# TimerSchematicV1.net
KiCad netlist of a schematic drawn in EAGLE
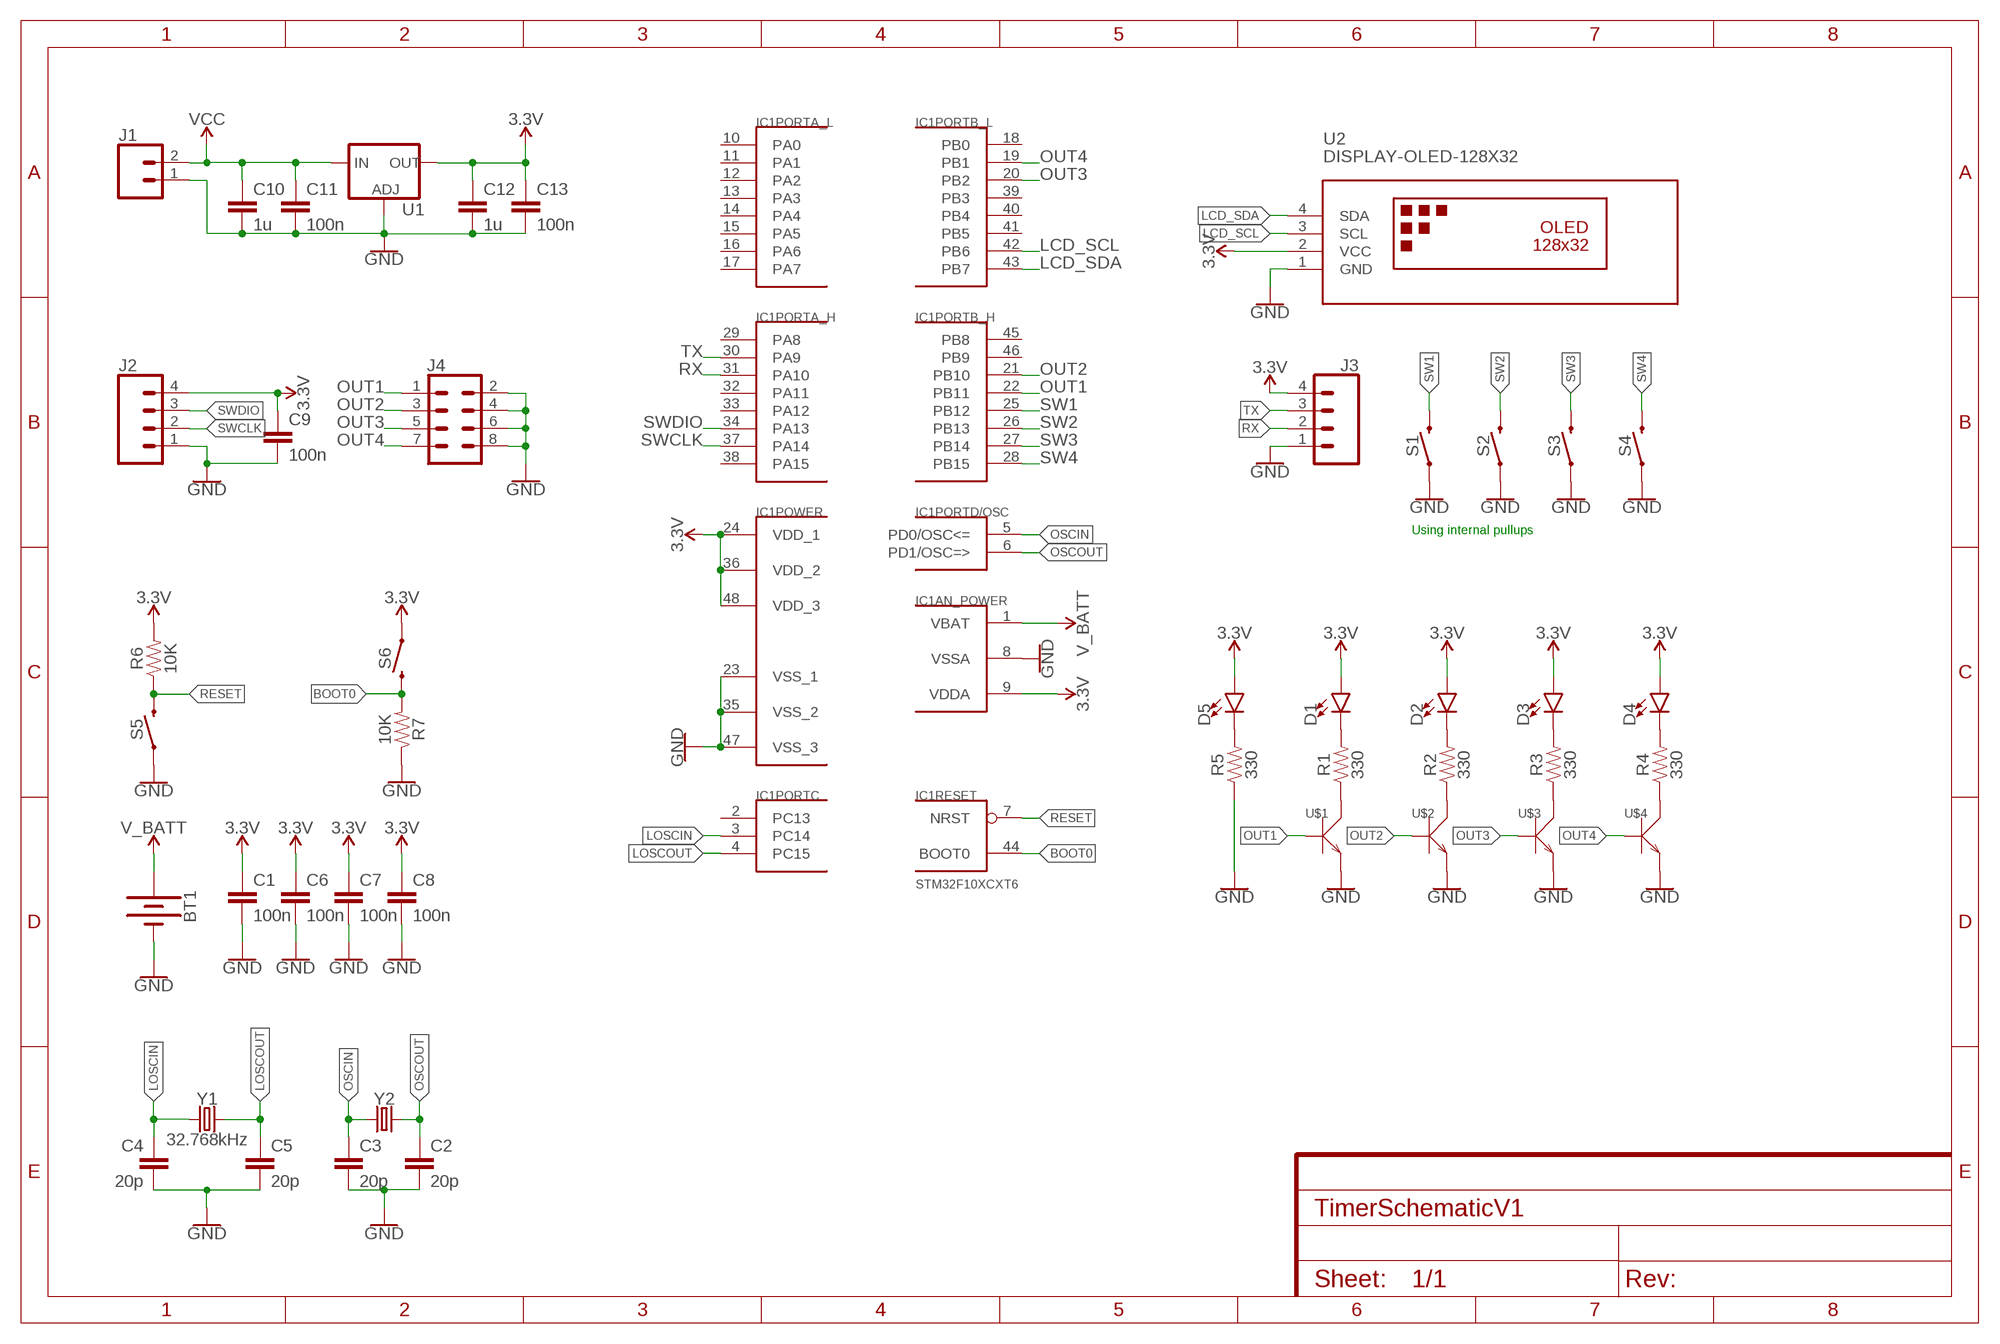
[diagram p0: schematic, sheet 1]

(export (version "E")
  (design (tool "Eeschema 10.0.6"))
  (components
    (comp (ref "BT1")
      (value "BATTERY-20MM_PTH")
      (footprint "eagle-import:BATTCOM_20MM_PTH")
      (libsource (lib "eagle-import") (part "BATTERY-20MM_PTH"))
    )
    (comp (ref "C1")
      (value "100n")
      (footprint "eagle-import:1206")
      (libsource (lib "eagle-import") (part "CAP-1206"))
    )
    (comp (ref "C2")
      (value "20p")
      (footprint "eagle-import:1206")
      (libsource (lib "eagle-import") (part "CAP-1206"))
    )
    (comp (ref "C3")
      (value "20p")
      (footprint "eagle-import:1206")
      (libsource (lib "eagle-import") (part "CAP-1206"))
    )
    (comp (ref "C4")
      (value "20p")
      (footprint "eagle-import:1206")
      (libsource (lib "eagle-import") (part "CAP-1206"))
    )
    (comp (ref "C5")
      (value "20p")
      (footprint "eagle-import:1206")
      (libsource (lib "eagle-import") (part "CAP-1206"))
    )
    (comp (ref "C6")
      (value "100n")
      (footprint "eagle-import:1206")
      (libsource (lib "eagle-import") (part "CAP-1206"))
    )
    (comp (ref "C7")
      (value "100n")
      (footprint "eagle-import:1206")
      (libsource (lib "eagle-import") (part "CAP-1206"))
    )
    (comp (ref "C8")
      (value "100n")
      (footprint "eagle-import:1206")
      (libsource (lib "eagle-import") (part "CAP-1206"))
    )
    (comp (ref "C9")
      (value "100n")
      (footprint "eagle-import:1206")
      (libsource (lib "eagle-import") (part "CAP-1206"))
    )
    (comp (ref "C10")
      (value "1u")
      (footprint "eagle-import:1206")
      (libsource (lib "eagle-import") (part "CAP-1206"))
    )
    (comp (ref "C11")
      (value "100n")
      (footprint "eagle-import:1206")
      (libsource (lib "eagle-import") (part "CAP-1206"))
    )
    (comp (ref "C12")
      (value "1u")
      (footprint "eagle-import:1206")
      (libsource (lib "eagle-import") (part "CAP-1206"))
    )
    (comp (ref "C13")
      (value "100n")
      (footprint "eagle-import:1206")
      (libsource (lib "eagle-import") (part "CAP-1206"))
    )
    (comp (ref "D1")
      (value "LED1206")
      (footprint "eagle-import:LED-1206")
      (libsource (lib "eagle-import") (part "LED1206"))
    )
    (comp (ref "D2")
      (value "LED1206")
      (footprint "eagle-import:LED-1206")
      (libsource (lib "eagle-import") (part "LED1206"))
    )
    (comp (ref "D3")
      (value "LED1206")
      (footprint "eagle-import:LED-1206")
      (libsource (lib "eagle-import") (part "LED1206"))
    )
    (comp (ref "D4")
      (value "LED1206")
      (footprint "eagle-import:LED-1206")
      (libsource (lib "eagle-import") (part "LED1206"))
    )
    (comp (ref "D5")
      (value "LED1206")
      (footprint "eagle-import:LED-1206")
      (libsource (lib "eagle-import") (part "LED1206"))
    )
    (comp (ref "IC1")
      (value "STM32F10XCXT6")
      (footprint "eagle-import:TQFP48")
      (libsource (lib "eagle-import") (part "STM32F10XCXT6"))
    )
    (comp (ref "J1")
      (value "CONN_02")
      (footprint "eagle-import:1X02")
      (libsource (lib "eagle-import") (part "CONN_02"))
    )
    (comp (ref "J2")
      (value "CONN_04PTH")
      (footprint "eagle-import:1X04")
      (libsource (lib "eagle-import") (part "CONN_04PTH"))
    )
    (comp (ref "J3")
      (value "CONN_04PTH")
      (footprint "eagle-import:1X04")
      (libsource (lib "eagle-import") (part "CONN_04PTH"))
    )
    (comp (ref "J4")
      (value "CONN_04X2")
      (footprint "eagle-import:2X4")
      (libsource (lib "eagle-import") (part "CONN_04X2"))
    )
    (comp (ref "R1")
      (value "330")
      (footprint "eagle-import:1206")
      (libsource (lib "eagle-import") (part "RESISTOR1206"))
    )
    (comp (ref "R2")
      (value "330")
      (footprint "eagle-import:1206")
      (libsource (lib "eagle-import") (part "RESISTOR1206"))
    )
    (comp (ref "R3")
      (value "330")
      (footprint "eagle-import:1206")
      (libsource (lib "eagle-import") (part "RESISTOR1206"))
    )
    (comp (ref "R4")
      (value "330")
      (footprint "eagle-import:1206")
      (libsource (lib "eagle-import") (part "RESISTOR1206"))
    )
    (comp (ref "R5")
      (value "330")
      (footprint "eagle-import:1206")
      (libsource (lib "eagle-import") (part "RESISTOR1206"))
    )
    (comp (ref "R6")
      (value "10K")
      (footprint "eagle-import:1206")
      (libsource (lib "eagle-import") (part "RESISTOR1206"))
    )
    (comp (ref "R7")
      (value "10K")
      (footprint "eagle-import:1206")
      (libsource (lib "eagle-import") (part "RESISTOR1206"))
    )
    (comp (ref "S1")
      (value "MOMENTARY-SWITCH-SPST-PTH-6.0MM-KIT")
      (footprint "eagle-import:TACTILE_SWITCH_PTH_6.0MM_KIT")
      (libsource (lib "eagle-import") (part "MOMENTARY-SWITCH-SPST-PTH-6.0MM-KIT"))
    )
    (comp (ref "S2")
      (value "MOMENTARY-SWITCH-SPST-PTH-6.0MM-KIT")
      (footprint "eagle-import:TACTILE_SWITCH_PTH_6.0MM_KIT")
      (libsource (lib "eagle-import") (part "MOMENTARY-SWITCH-SPST-PTH-6.0MM-KIT"))
    )
    (comp (ref "S3")
      (value "MOMENTARY-SWITCH-SPST-PTH-6.0MM-KIT")
      (footprint "eagle-import:TACTILE_SWITCH_PTH_6.0MM_KIT")
      (libsource (lib "eagle-import") (part "MOMENTARY-SWITCH-SPST-PTH-6.0MM-KIT"))
    )
    (comp (ref "S4")
      (value "MOMENTARY-SWITCH-SPST-PTH-6.0MM-KIT")
      (footprint "eagle-import:TACTILE_SWITCH_PTH_6.0MM_KIT")
      (libsource (lib "eagle-import") (part "MOMENTARY-SWITCH-SPST-PTH-6.0MM-KIT"))
    )
    (comp (ref "S5")
      (value "MOMENTARY-SWITCH-SPST-SMD-6.0X3.5MM")
      (footprint "eagle-import:TACTILE_SWITCH_SMD_6.0X3.5MM")
      (libsource (lib "eagle-import") (part "MOMENTARY-SWITCH-SPST-SMD-6.0X3.5MM"))
    )
    (comp (ref "S6")
      (value "MOMENTARY-SWITCH-SPST-SMD-6.0X3.5MM")
      (footprint "eagle-import:TACTILE_SWITCH_SMD_6.0X3.5MM")
      (libsource (lib "eagle-import") (part "MOMENTARY-SWITCH-SPST-SMD-6.0X3.5MM"))
    )
    (comp (ref "U$1")
      (value "MMBT3904LT1G")
      (footprint "eagle-import:SOT-23")
      (libsource (lib "eagle-import") (part "SMD-TRANSISTORS-NPN-40V-200MA-MMBT3904LT1G(SOT-23)"))
    )
    (comp (ref "U$2")
      (value "MMBT3904LT1G")
      (footprint "eagle-import:SOT-23")
      (libsource (lib "eagle-import") (part "SMD-TRANSISTORS-NPN-40V-200MA-MMBT3904LT1G(SOT-23)"))
    )
    (comp (ref "U$3")
      (value "MMBT3904LT1G")
      (footprint "eagle-import:SOT-23")
      (libsource (lib "eagle-import") (part "SMD-TRANSISTORS-NPN-40V-200MA-MMBT3904LT1G(SOT-23)"))
    )
    (comp (ref "U$4")
      (value "MMBT3904LT1G")
      (footprint "eagle-import:SOT-23")
      (libsource (lib "eagle-import") (part "SMD-TRANSISTORS-NPN-40V-200MA-MMBT3904LT1G(SOT-23)"))
    )
    (comp (ref "U1")
      (value "V_REG_LM1117SOT223")
      (footprint "eagle-import:SOT223")
      (libsource (lib "eagle-import") (part "V_REG_LM1117SOT223"))
    )
    (comp (ref "U2")
      (value "DISPLAY-OLED-128X32")
      (footprint "eagle-import:DISPLAY-OLED-128X32")
      (libsource (lib "eagle-import") (part "DISPLAY-OLED-128X32"))
    )
    (comp (ref "Y1")
      (value "32.768kHz")
      (footprint "eagle-import:CRYSTAL-PTH-2X6-CYL-KIT")
      (libsource (lib "eagle-import") (part "CRYSTAL-32.768KHZPTH-2X6-KIT"))
    )
    (comp (ref "Y2")
      (value "CRYSTALSMD-HC49UP")
      (footprint "eagle-import:HC49UP")
      (libsource (lib "eagle-import") (part "CRYSTALSMD-HC49UP"))
    )
  )
  (nets
    (net (code "1") (name "3.3V") (class "Default")
      (node (ref "C1") (pin "1") (pinfunction "1_1") (pintype "passive"))
      (node (ref "C12") (pin "1") (pinfunction "1_1") (pintype "passive"))
      (node (ref "C13") (pin "1") (pinfunction "1_1") (pintype "passive"))
      (node (ref "C6") (pin "1") (pinfunction "1_1") (pintype "passive"))
      (node (ref "C7") (pin "1") (pinfunction "1_1") (pintype "passive"))
      (node (ref "C8") (pin "1") (pinfunction "1_1") (pintype "passive"))
      (node (ref "C9") (pin "1") (pinfunction "1_1") (pintype "passive"))
      (node (ref "D1") (pin "A") (pinfunction "A_A") (pintype "passive"))
      (node (ref "D2") (pin "A") (pinfunction "A_A") (pintype "passive"))
      (node (ref "D3") (pin "A") (pinfunction "A_A") (pintype "passive"))
      (node (ref "D4") (pin "A") (pinfunction "A_A") (pintype "passive"))
      (node (ref "D5") (pin "A") (pinfunction "A_A") (pintype "passive"))
      (node (ref "IC1") (pin "24") (pinfunction "VDD_1_24") (pintype "power_in"))
      (node (ref "IC1") (pin "36") (pinfunction "VDD_2_36") (pintype "power_in"))
      (node (ref "IC1") (pin "48") (pinfunction "VDD_3_48") (pintype "power_in"))
      (node (ref "IC1") (pin "9") (pinfunction "VDDA_9") (pintype "power_in"))
      (node (ref "J2") (pin "4") (pinfunction "4_4") (pintype "passive"))
      (node (ref "J3") (pin "4") (pinfunction "4_4") (pintype "passive"))
      (node (ref "R6") (pin "2") (pinfunction "2_2") (pintype "passive"))
      (node (ref "S6") (pin "1") (pinfunction "1_1") (pintype "passive"))
      (node (ref "U1") (pin "2") (pinfunction "OUT_2") (pintype "output"))
      (node (ref "U1") (pin "4") (pinfunction "OUT_4") (pintype "output"))
      (node (ref "U2") (pin "2") (pinfunction "VCC_2") (pintype "power_in"))
    )
    (net (code "2") (name "BOOT0") (class "Default")
      (node (ref "IC1") (pin "44") (pinfunction "BOOT0_44") (pintype "input"))
      (node (ref "R7") (pin "2") (pinfunction "2_2") (pintype "passive"))
      (node (ref "S6") (pin "2") (pinfunction "2_2") (pintype "passive"))
    )
    (net (code "3") (name "GND") (class "Default")
      (node (ref "BT1") (pin "2") (pinfunction "-_2") (pintype "power_in"))
      (node (ref "C1") (pin "2") (pinfunction "2_2") (pintype "passive"))
      (node (ref "C10") (pin "2") (pinfunction "2_2") (pintype "passive"))
      (node (ref "C11") (pin "2") (pinfunction "2_2") (pintype "passive"))
      (node (ref "C12") (pin "2") (pinfunction "2_2") (pintype "passive"))
      (node (ref "C13") (pin "2") (pinfunction "2_2") (pintype "passive"))
      (node (ref "C2") (pin "2") (pinfunction "2_2") (pintype "passive"))
      (node (ref "C3") (pin "2") (pinfunction "2_2") (pintype "passive"))
      (node (ref "C4") (pin "2") (pinfunction "2_2") (pintype "passive"))
      (node (ref "C5") (pin "2") (pinfunction "2_2") (pintype "passive"))
      (node (ref "C6") (pin "2") (pinfunction "2_2") (pintype "passive"))
      (node (ref "C7") (pin "2") (pinfunction "2_2") (pintype "passive"))
      (node (ref "C8") (pin "2") (pinfunction "2_2") (pintype "passive"))
      (node (ref "C9") (pin "2") (pinfunction "2_2") (pintype "passive"))
      (node (ref "IC1") (pin "23") (pinfunction "VSS_1_23") (pintype "power_in"))
      (node (ref "IC1") (pin "35") (pinfunction "VSS_2_35") (pintype "power_in"))
      (node (ref "IC1") (pin "47") (pinfunction "VSS_3_47") (pintype "power_in"))
      (node (ref "IC1") (pin "8") (pinfunction "VSSA_8") (pintype "power_in"))
      (node (ref "J1") (pin "1") (pinfunction "1_1") (pintype "passive"))
      (node (ref "J2") (pin "1") (pinfunction "1_1") (pintype "passive"))
      (node (ref "J3") (pin "1") (pinfunction "1_1") (pintype "passive"))
      (node (ref "J4") (pin "2") (pinfunction "2_2") (pintype "passive"))
      (node (ref "J4") (pin "4") (pinfunction "4_4") (pintype "passive"))
      (node (ref "J4") (pin "6") (pinfunction "6_6") (pintype "passive"))
      (node (ref "J4") (pin "8") (pinfunction "8_8") (pintype "passive"))
      (node (ref "R5") (pin "1") (pinfunction "1_1") (pintype "passive"))
      (node (ref "R7") (pin "1") (pinfunction "1_1") (pintype "passive"))
      (node (ref "S1") (pin "1") (pinfunction "1_1") (pintype "passive"))
      (node (ref "S2") (pin "1") (pinfunction "1_1") (pintype "passive"))
      (node (ref "S3") (pin "1") (pinfunction "1_1") (pintype "passive"))
      (node (ref "S4") (pin "1") (pinfunction "1_1") (pintype "passive"))
      (node (ref "S5") (pin "1") (pinfunction "1_1") (pintype "passive"))
      (node (ref "U$1") (pin "2") (pinfunction "E_2") (pintype "passive"))
      (node (ref "U$2") (pin "2") (pinfunction "E_2") (pintype "passive"))
      (node (ref "U$3") (pin "2") (pinfunction "E_2") (pintype "passive"))
      (node (ref "U$4") (pin "2") (pinfunction "E_2") (pintype "passive"))
      (node (ref "U1") (pin "1") (pinfunction "ADJ_1") (pintype "input"))
      (node (ref "U2") (pin "1") (pinfunction "GND_1") (pintype "power_in"))
    )
    (net (code "4") (name "LCD_SCL") (class "Default")
      (node (ref "IC1") (pin "42") (pinfunction "PB6_42") (pintype "bidirectional"))
      (node (ref "U2") (pin "3") (pinfunction "SCL_3") (pintype "bidirectional"))
    )
    (net (code "5") (name "LCD_SDA") (class "Default")
      (node (ref "IC1") (pin "43") (pinfunction "PB7_43") (pintype "bidirectional"))
      (node (ref "U2") (pin "4") (pinfunction "SDA_4") (pintype "bidirectional"))
    )
    (net (code "6") (name "LOSCIN") (class "Default")
      (node (ref "C4") (pin "1") (pinfunction "1_1") (pintype "passive"))
      (node (ref "IC1") (pin "3") (pinfunction "PC14_3") (pintype "bidirectional"))
      (node (ref "Y1") (pin "1") (pinfunction "1_1") (pintype "passive"))
    )
    (net (code "7") (name "LOSCOUT") (class "Default")
      (node (ref "C5") (pin "1") (pinfunction "1_1") (pintype "passive"))
      (node (ref "IC1") (pin "4") (pinfunction "PC15_4") (pintype "bidirectional"))
      (node (ref "Y1") (pin "2") (pinfunction "2_2") (pintype "passive"))
    )
    (net (code "8") (name "Net-(D1-PadC)") (class "Default")
      (node (ref "D1") (pin "C") (pinfunction "C_C") (pintype "passive"))
      (node (ref "R1") (pin "2") (pinfunction "2_2") (pintype "passive"))
    )
    (net (code "9") (name "Net-(D2-PadC)") (class "Default")
      (node (ref "D2") (pin "C") (pinfunction "C_C") (pintype "passive"))
      (node (ref "R2") (pin "2") (pinfunction "2_2") (pintype "passive"))
    )
    (net (code "10") (name "Net-(D3-PadC)") (class "Default")
      (node (ref "D3") (pin "C") (pinfunction "C_C") (pintype "passive"))
      (node (ref "R3") (pin "2") (pinfunction "2_2") (pintype "passive"))
    )
    (net (code "11") (name "Net-(D4-PadC)") (class "Default")
      (node (ref "D4") (pin "C") (pinfunction "C_C") (pintype "passive"))
      (node (ref "R4") (pin "2") (pinfunction "2_2") (pintype "passive"))
    )
    (net (code "12") (name "Net-(D5-PadC)") (class "Default")
      (node (ref "D5") (pin "C") (pinfunction "C_C") (pintype "passive"))
      (node (ref "R5") (pin "2") (pinfunction "2_2") (pintype "passive"))
    )
    (net (code "13") (name "Net-(U$1-C)") (class "Default")
      (node (ref "R1") (pin "1") (pinfunction "1_1") (pintype "passive"))
      (node (ref "U$1") (pin "3") (pinfunction "C_3") (pintype "passive"))
    )
    (net (code "14") (name "Net-(U$2-C)") (class "Default")
      (node (ref "R2") (pin "1") (pinfunction "1_1") (pintype "passive"))
      (node (ref "U$2") (pin "3") (pinfunction "C_3") (pintype "passive"))
    )
    (net (code "15") (name "Net-(U$3-C)") (class "Default")
      (node (ref "R3") (pin "1") (pinfunction "1_1") (pintype "passive"))
      (node (ref "U$3") (pin "3") (pinfunction "C_3") (pintype "passive"))
    )
    (net (code "16") (name "Net-(U$4-C)") (class "Default")
      (node (ref "R4") (pin "1") (pinfunction "1_1") (pintype "passive"))
      (node (ref "U$4") (pin "3") (pinfunction "C_3") (pintype "passive"))
    )
    (net (code "17") (name "OSCIN") (class "Default")
      (node (ref "C3") (pin "1") (pinfunction "1_1") (pintype "passive"))
      (node (ref "IC1") (pin "5") (pinfunction "PD0/OSC<=_5") (pintype "bidirectional"))
      (node (ref "Y2") (pin "1") (pinfunction "1_1") (pintype "passive"))
    )
    (net (code "18") (name "OSCOUT") (class "Default")
      (node (ref "C2") (pin "1") (pinfunction "1_1") (pintype "passive"))
      (node (ref "IC1") (pin "6") (pinfunction "PD1/OSC=>_6") (pintype "bidirectional"))
      (node (ref "Y2") (pin "2") (pinfunction "2_2") (pintype "passive"))
    )
    (net (code "19") (name "OUT1") (class "Default")
      (node (ref "IC1") (pin "22") (pinfunction "PB11_22") (pintype "bidirectional"))
      (node (ref "J4") (pin "1") (pinfunction "1_1") (pintype "passive"))
      (node (ref "U$1") (pin "1") (pinfunction "B_1") (pintype "passive"))
    )
    (net (code "20") (name "OUT2") (class "Default")
      (node (ref "IC1") (pin "21") (pinfunction "PB10_21") (pintype "bidirectional"))
      (node (ref "J4") (pin "3") (pinfunction "3_3") (pintype "passive"))
      (node (ref "U$2") (pin "1") (pinfunction "B_1") (pintype "passive"))
    )
    (net (code "21") (name "OUT3") (class "Default")
      (node (ref "IC1") (pin "20") (pinfunction "PB2_20") (pintype "bidirectional"))
      (node (ref "J4") (pin "5") (pinfunction "5_5") (pintype "passive"))
      (node (ref "U$3") (pin "1") (pinfunction "B_1") (pintype "passive"))
    )
    (net (code "22") (name "OUT4") (class "Default")
      (node (ref "IC1") (pin "19") (pinfunction "PB1_19") (pintype "bidirectional"))
      (node (ref "J4") (pin "7") (pinfunction "7_7") (pintype "passive"))
      (node (ref "U$4") (pin "1") (pinfunction "B_1") (pintype "passive"))
    )
    (net (code "23") (name "RESET") (class "Default")
      (node (ref "IC1") (pin "7") (pinfunction "NRST_7") (pintype "input"))
      (node (ref "R6") (pin "1") (pinfunction "1_1") (pintype "passive"))
      (node (ref "S5") (pin "2") (pinfunction "2_2") (pintype "passive"))
    )
    (net (code "24") (name "RX") (class "Default")
      (node (ref "IC1") (pin "31") (pinfunction "PA10_31") (pintype "bidirectional"))
      (node (ref "J3") (pin "2") (pinfunction "2_2") (pintype "passive"))
    )
    (net (code "25") (name "SW1") (class "Default")
      (node (ref "IC1") (pin "25") (pinfunction "PB12_25") (pintype "bidirectional"))
      (node (ref "S1") (pin "3") (pinfunction "2_3") (pintype "passive"))
    )
    (net (code "26") (name "SW2") (class "Default")
      (node (ref "IC1") (pin "26") (pinfunction "PB13_26") (pintype "bidirectional"))
      (node (ref "S2") (pin "3") (pinfunction "2_3") (pintype "passive"))
    )
    (net (code "27") (name "SW3") (class "Default")
      (node (ref "IC1") (pin "27") (pinfunction "PB14_27") (pintype "bidirectional"))
      (node (ref "S3") (pin "3") (pinfunction "2_3") (pintype "passive"))
    )
    (net (code "28") (name "SW4") (class "Default")
      (node (ref "IC1") (pin "28") (pinfunction "PB15_28") (pintype "bidirectional"))
      (node (ref "S4") (pin "3") (pinfunction "2_3") (pintype "passive"))
    )
    (net (code "29") (name "SWCLK") (class "Default")
      (node (ref "IC1") (pin "37") (pinfunction "PA14_37") (pintype "bidirectional"))
      (node (ref "J2") (pin "2") (pinfunction "2_2") (pintype "passive"))
    )
    (net (code "30") (name "SWDIO") (class "Default")
      (node (ref "IC1") (pin "34") (pinfunction "PA13_34") (pintype "bidirectional"))
      (node (ref "J2") (pin "3") (pinfunction "3_3") (pintype "passive"))
    )
    (net (code "31") (name "TX") (class "Default")
      (node (ref "IC1") (pin "30") (pinfunction "PA9_30") (pintype "bidirectional"))
      (node (ref "J3") (pin "3") (pinfunction "3_3") (pintype "passive"))
    )
    (net (code "32") (name "VCC") (class "Default")
      (node (ref "C10") (pin "1") (pinfunction "1_1") (pintype "passive"))
      (node (ref "C11") (pin "1") (pinfunction "1_1") (pintype "passive"))
      (node (ref "J1") (pin "2") (pinfunction "2_2") (pintype "passive"))
      (node (ref "U1") (pin "3") (pinfunction "IN_3") (pintype "input"))
    )
    (net (code "33") (name "V_BATT") (class "Default")
      (node (ref "BT1") (pin "1") (pinfunction "+_1") (pintype "power_in"))
      (node (ref "IC1") (pin "1") (pinfunction "VBAT_1") (pintype "power_in"))
    )
    (net (code "34") (name "unconnected-(IC1B-PA8-Pad29)") (class "Default")
      (node (ref "IC1") (pin "29") (pinfunction "PA8_29") (pintype "bidirectional"))
    )
    (net (code "35") (name "unconnected-(IC1B-PA11-Pad32)") (class "Default")
      (node (ref "IC1") (pin "32") (pinfunction "PA11_32") (pintype "bidirectional"))
    )
    (net (code "36") (name "unconnected-(IC1B-PA12-Pad33)") (class "Default")
      (node (ref "IC1") (pin "33") (pinfunction "PA12_33") (pintype "bidirectional"))
    )
    (net (code "37") (name "unconnected-(IC1B-PA15-Pad38)") (class "Default")
      (node (ref "IC1") (pin "38") (pinfunction "PA15_38") (pintype "bidirectional"))
    )
    (net (code "38") (name "unconnected-(IC1C-PA0-Pad10)") (class "Default")
      (node (ref "IC1") (pin "10") (pinfunction "PA0_10") (pintype "bidirectional"))
    )
    (net (code "39") (name "unconnected-(IC1C-PA1-Pad11)") (class "Default")
      (node (ref "IC1") (pin "11") (pinfunction "PA1_11") (pintype "bidirectional"))
    )
    (net (code "40") (name "unconnected-(IC1C-PA2-Pad12)") (class "Default")
      (node (ref "IC1") (pin "12") (pinfunction "PA2_12") (pintype "bidirectional"))
    )
    (net (code "41") (name "unconnected-(IC1C-PA3-Pad13)") (class "Default")
      (node (ref "IC1") (pin "13") (pinfunction "PA3_13") (pintype "bidirectional"))
    )
    (net (code "42") (name "unconnected-(IC1C-PA4-Pad14)") (class "Default")
      (node (ref "IC1") (pin "14") (pinfunction "PA4_14") (pintype "bidirectional"))
    )
    (net (code "43") (name "unconnected-(IC1C-PA5-Pad15)") (class "Default")
      (node (ref "IC1") (pin "15") (pinfunction "PA5_15") (pintype "bidirectional"))
    )
    (net (code "44") (name "unconnected-(IC1C-PA6-Pad16)") (class "Default")
      (node (ref "IC1") (pin "16") (pinfunction "PA6_16") (pintype "bidirectional"))
    )
    (net (code "45") (name "unconnected-(IC1C-PA7-Pad17)") (class "Default")
      (node (ref "IC1") (pin "17") (pinfunction "PA7_17") (pintype "bidirectional"))
    )
    (net (code "46") (name "unconnected-(IC1D-PB8-Pad45)") (class "Default")
      (node (ref "IC1") (pin "45") (pinfunction "PB8_45") (pintype "bidirectional"))
    )
    (net (code "47") (name "unconnected-(IC1D-PB9-Pad46)") (class "Default")
      (node (ref "IC1") (pin "46") (pinfunction "PB9_46") (pintype "bidirectional"))
    )
    (net (code "48") (name "unconnected-(IC1E-PB0-Pad18)") (class "Default")
      (node (ref "IC1") (pin "18") (pinfunction "PB0_18") (pintype "bidirectional"))
    )
    (net (code "49") (name "unconnected-(IC1E-PB3-Pad39)") (class "Default")
      (node (ref "IC1") (pin "39") (pinfunction "PB3_39") (pintype "bidirectional"))
    )
    (net (code "50") (name "unconnected-(IC1E-PB4-Pad40)") (class "Default")
      (node (ref "IC1") (pin "40") (pinfunction "PB4_40") (pintype "bidirectional"))
    )
    (net (code "51") (name "unconnected-(IC1E-PB5-Pad41)") (class "Default")
      (node (ref "IC1") (pin "41") (pinfunction "PB5_41") (pintype "bidirectional"))
    )
    (net (code "52") (name "unconnected-(IC1F-PC13-Pad2)") (class "Default")
      (node (ref "IC1") (pin "2") (pinfunction "PC13_2") (pintype "bidirectional"))
    )
  )
)
